# DAUGHTERBOARD.net
KiCad netlist of a schematic drawn in Altium Designer
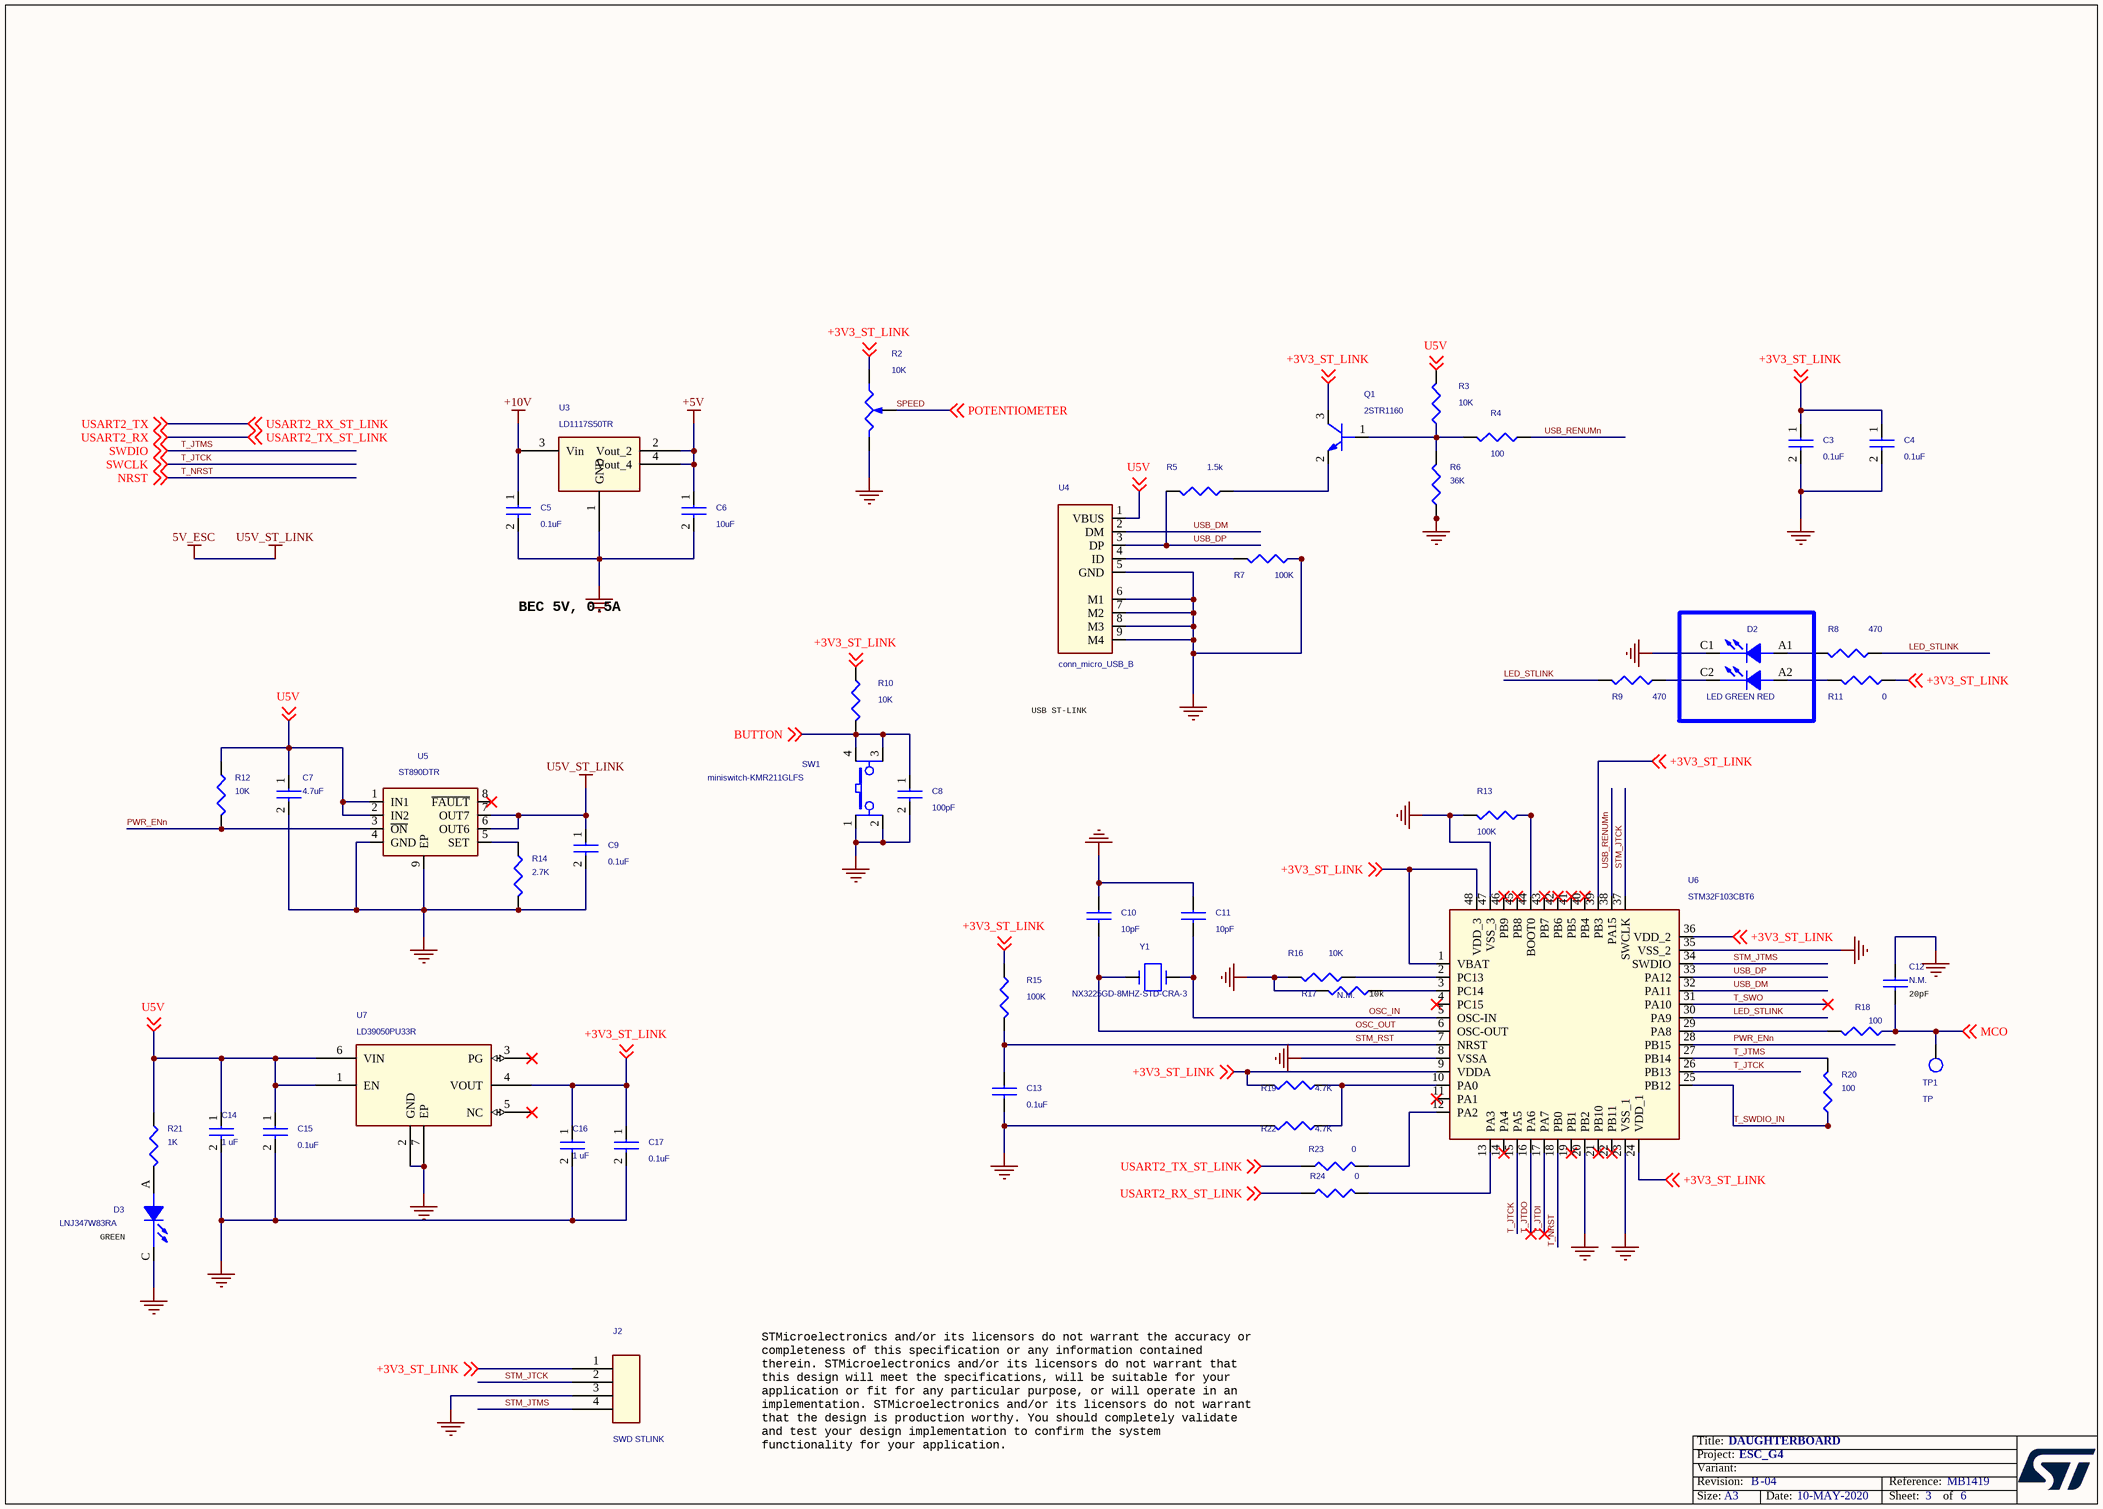
[diagram p0: DAUGHTERBOARD.SchDoc]

(export (version "E")
  (design (tool "Eeschema 10.0.6"))
  (components
    (comp (ref "C3")
      (value "0.1uF")
      (footprint "C_0402")
      (description "CAP CER 0.1UF 16V X7R 0402")
      (fields (field (name "MANUFACTURER") "Wurth Electronics Inc.") (field (name "TOLERANCE") "10%"))
      (libsource (lib "*") (part "CAP_Dup1"))
    )
    (comp (ref "C4")
      (value "0.1uF")
      (footprint "C_0402")
      (description "CAP CER 0.1UF 16V X7R 0402")
      (fields (field (name "MANUFACTURER") "Wurth Electronics Inc.") (field (name "TOLERANCE") "10%"))
      (libsource (lib "*") (part "CAP_Dup1"))
    )
    (comp (ref "C5")
      (value "0.1uF")
      (footprint "C_0402")
      (description "CAP CER 0.1UF 16V X7R 0402")
      (fields (field (name "MANUFACTURER") "Wurth Electronics Inc.") (field (name "TOLERANCE") "10%"))
      (libsource (lib "*") (part "CAP_Dup1"))
    )
    (comp (ref "C6")
      (value "10uF")
      (footprint "C_0805")
      (description "CAP CER 10UF 16V X5R 0805")
      (fields (field (name "MANUFACTURER") "Wurth Electronics Inc.") (field (name "TOLERANCE") "20%"))
      (libsource (lib "*") (part "CAP_Dup1"))
    )
    (comp (ref "C7")
      (value "4.7uF")
      (footprint "C_0805")
      (description "CAP CER 4.7UF 16V X5R 0805")
      (fields (field (name "PART_NUMBER") "TMP-410") (field (name "TOLERANCE") "20%"))
      (libsource (lib "*") (part "CAP_Dup1"))
    )
    (comp (ref "C8")
      (value "100pF")
      (footprint "C_0402")
      (description "CAP CER 100PF 10V C0G/NP0 0402")
      (fields (field (name "PART_NUMBER") "TMP-412") (field (name "TOLERANCE") "5%"))
      (libsource (lib "*") (part "CAP_Dup1"))
    )
    (comp (ref "C9")
      (value "0.1uF")
      (footprint "C_0402")
      (description "CAP CER 0.1UF 16V X7R 0402")
      (fields (field (name "MANUFACTURER") "Wurth Electronics Inc.") (field (name "TOLERANCE") "10%"))
      (libsource (lib "*") (part "CAP_Dup1"))
    )
    (comp (ref "C10")
      (value "10pF")
      (footprint "C_0402")
      (description "CAP CER 10PF 10V C0G/NP0 0402")
      (fields (field (name "PART_NUMBER") "TMP-395") (field (name "TOLERANCE") "5%"))
      (libsource (lib "*") (part "CAP_7"))
    )
    (comp (ref "C11")
      (value "10pF")
      (footprint "C_0402")
      (description "CAP CER 10PF 10V C0G/NP0 0402")
      (fields (field (name "PART_NUMBER") "TMP-395") (field (name "TOLERANCE") "5%"))
      (libsource (lib "*") (part "CAP_7"))
    )
    (comp (ref "C12")
      (value "N.M.")
      (footprint "C_0402")
      (description "CAP CER 0402-NOT MOUNTED")
      (fields (field (name "PART_NUMBER") "TMP-408"))
      (libsource (lib "*") (part "CAP_6"))
    )
    (comp (ref "C13")
      (value "0.1uF")
      (footprint "C_0402")
      (description "CAP CER 0.1UF 16V X7R 0402")
      (fields (field (name "PART_NUMBER") "CAP-00000053") (field (name "TOLERANCE") "10%"))
      (libsource (lib "*") (part "CAP_8"))
    )
    (comp (ref "C14")
      (value "1 uF")
      (footprint "C_0603")
      (description "CAP CER 1UF 16V X5R 0603")
      (fields (field (name "PART_NUMBER") "TMP-302") (field (name "TOLERANCE") "10%"))
      (libsource (lib "*") (part "CAP_Dup1"))
    )
    (comp (ref "C15")
      (value "0.1uF")
      (footprint "C_0603")
      (description "CAP CER 0.1UF 16V X7R 0603")
      (fields (field (name "MANUFACTURER") "Wurth Electronics Inc.") (field (name "TOLERANCE") "10%"))
      (libsource (lib "*") (part "CAP_Dup1"))
    )
    (comp (ref "C16")
      (value "1 uF")
      (footprint "C_0603")
      (description "CAP CER 1UF 16V X5R 0603")
      (fields (field (name "PART_NUMBER") "TMP-302") (field (name "TOLERANCE") "10%"))
      (libsource (lib "*") (part "CAP_Dup1"))
    )
    (comp (ref "C17")
      (value "0.1uF")
      (footprint "C_0402")
      (description "CAP CER 0.1UF 16V X7R 0402")
      (fields (field (name "PART_NUMBER") "CAP-00000053") (field (name "TOLERANCE") "10%"))
      (libsource (lib "*") (part "CAP_Dup1"))
    )
    (comp (ref "D2")
      (value "LED GREEN RED")
      (footprint "Led_bicolor_3528-PLCC-4")
      (description "LED GREEN/RED CLEAR 4PLCC SMD")
      (fields (field (name "PART_NUMBER") "TMP-705") (field (name "MANUFACTURER") "Wurth Electronics Inc."))
      (libsource (lib "*") (part "LED_BICOLOR"))
    )
    (comp (ref "D3")
      (value "LNJ347W83RA")
      (footprint "D_0402_Led_green")
      (description "LED GREEN 0402 SMD")
      (fields
        (field (name "MANUFACTURER") "Panasonic Electronic Components")
        (field (name "PART_NUMBER") "TMP-187")
      )
      (libsource (lib "*") (part "LED"))
    )
    (comp (ref "J2")
      (value "SWD STLINK")
      (footprint "strip4_100m_v")
      (description "SOLDER PADS")
      (libsource (lib "*") (part "CON4"))
    )
    (comp (ref "Q1")
      (value "2STR1160")
      (footprint "sot23-3p97_255x140l40x40n")
      (description "TRANS NPN 60V 1A SOT-23")
      (fields (field (name "PART_NUMBER") "TMP-433") (field (name "MANUFACTURER") "STMicroelectronics"))
      (libsource (lib "*") (part "BJT_NPN_BEC"))
    )
    (comp (ref "R2")
      (value "10K")
      (footprint "trimmer-3386P_T")
      (description "TRIMMER 10K OHM 0.5W PC PIN")
      (fields (field (name "PART_NUMBER") "TMP-491") (field (name "TOLERANCE") "10%"))
      (libsource (lib "*") (part "POT"))
    )
    (comp (ref "R3")
      (value "10K")
      (footprint "R_0402")
      (description "RES SMD 10K OHM 1% 1/16W 0402")
      (fields (field (name "MANUFACTURER") "Yageo") (field (name "TOLERANCE") "1%"))
      (libsource (lib "*") (part "RES"))
    )
    (comp (ref "R4")
      (value "100")
      (footprint "R_0402")
      (description "RES SMD 100 OHM 1% 1/16W 0402")
      (fields (field (name "PART_NUMBER") "TMP-406") (field (name "TOLERANCE") "1%"))
      (libsource (lib "*") (part "RES"))
    )
    (comp (ref "R5")
      (value "1.5k")
      (footprint "R_0402")
      (description "RES SMD 1.5K OHM 1% 1/16W 0402")
      (fields (field (name "PART_NUMBER") "TMP-393") (field (name "TOLERANCE") "1%"))
      (libsource (lib "*") (part "RES"))
    )
    (comp (ref "R6")
      (value "36K")
      (footprint "R_0402")
      (description "RES SMD 36K OHM 1% 1/16W 0402")
      (fields (field (name "MANUFACTURER") "Yageo") (field (name "TOLERANCE") "1%"))
      (libsource (lib "*") (part "RES"))
    )
    (comp (ref "R7")
      (value "100K")
      (footprint "R_0402")
      (description "RES SMD 100K OHM 1% 1/16W 0402")
      (fields (field (name "MANUFACTURER") "TE Connectivity Passive Product") (field (name "TOLERANCE") "1%"))
      (libsource (lib "*") (part "RES"))
    )
    (comp (ref "R8")
      (value "470")
      (footprint "R_0402")
      (description "RES SMD 100 OHM 1% 1/16W 0402")
      (fields (field (name "PART_NUMBER") "TMP-406") (field (name "TOLERANCE") "1%"))
      (libsource (lib "*") (part "RES"))
    )
    (comp (ref "R9")
      (value "470")
      (footprint "R_0402")
      (description "RES SMD 100 OHM 1% 1/16W 0402")
      (fields (field (name "MANUFACTURER") "TE Connectivity Passive Product") (field (name "TOLERANCE") "1%"))
      (libsource (lib "*") (part "RES"))
    )
    (comp (ref "R10")
      (value "10K")
      (footprint "R_0402")
      (description "RES SMD 10K OHM 1% 1/16W 0402")
      (fields (field (name "PART_NUMBER") "TMP-396") (field (name "TOLERANCE") "1%"))
      (libsource (lib "*") (part "RES"))
    )
    (comp (ref "R11")
      (value "0")
      (footprint "R_0402")
      (description "RES SMD 0 OHM JUMPER 1/16W 0402")
      (fields (field (name "MANUFACTURER") "Vishay Dale") (field (name "TOLERANCE") "Jumper"))
      (libsource (lib "*") (part "RES"))
    )
    (comp (ref "R12")
      (value "10K")
      (footprint "R_0402")
      (description "RES SMD 10K OHM 1% 1/16W 0402")
      (fields (field (name "MANUFACTURER") "Yageo") (field (name "TOLERANCE") "1%"))
      (libsource (lib "*") (part "RES"))
    )
    (comp (ref "R13")
      (value "100K")
      (footprint "R_0402")
      (description "RES SMD 100K OHM 1% 1/16W 0402")
      (fields (field (name "MANUFACTURER") "TE Connectivity Passive Product") (field (name "TOLERANCE") "1%"))
      (libsource (lib "*") (part "RES"))
    )
    (comp (ref "R14")
      (value "2.7K")
      (footprint "R_0402")
      (description "RES SMD 2.7K OHM 1% 1/16W 0402")
      (fields (field (name "PART_NUMBER") "TMP-411") (field (name "TOLERANCE") "1%"))
      (libsource (lib "*") (part "RES"))
    )
    (comp (ref "R15")
      (value "100K")
      (footprint "R_0402")
      (description "RES SMD 100K OHM 1% 1/16W 0402")
      (fields (field (name "PART_NUMBER") "TMP-405") (field (name "TOLERANCE") "1%"))
      (libsource (lib "*") (part "RES"))
    )
    (comp (ref "R16")
      (value "10K")
      (footprint "R_0402")
      (description "RES SMD 10K OHM 1% 1/16W 0402")
      (fields (field (name "PART_NUMBER") "TMP-396") (field (name "TOLERANCE") "1%"))
      (libsource (lib "*") (part "RES"))
    )
    (comp (ref "R17")
      (value "N.M.")
      (footprint "R_0402")
      (description "RES SMD 0402 - NOT MOUNTED")
      (fields (field (name "PART_NUMBER") "TMP-404"))
      (libsource (lib "*") (part "RES"))
    )
    (comp (ref "R18")
      (value "100")
      (footprint "R_0402")
      (description "RES SMD 100 OHM 1% 1/16W 0402")
      (fields (field (name "MANUFACTURER") "TE Connectivity Passive Product") (field (name "TOLERANCE") "1%"))
      (libsource (lib "*") (part "RES"))
    )
    (comp (ref "R19")
      (value "4.7K")
      (footprint "R_0402")
      (description "RES SMD 4.7K OHM 1% 1/16W 0402")
      (fields (field (name "PART_NUMBER") "TMP-403") (field (name "TOLERANCE") "1%"))
      (libsource (lib "*") (part "RES"))
    )
    (comp (ref "R20")
      (value "100")
      (footprint "R_0402")
      (description "RES SMD 100 OHM 1% 1/16W 0402")
      (fields (field (name "PART_NUMBER") "TMP-406") (field (name "TOLERANCE") "1%"))
      (libsource (lib "*") (part "RES"))
    )
    (comp (ref "R21")
      (value "1K")
      (footprint "R_0402")
      (description "RES SMD 1K OHM 1% 1/16W 0402")
      (fields (field (name "PART_NUMBER") "TMP-352") (field (name "TOLERANCE") "1%"))
      (libsource (lib "*") (part "RES"))
    )
    (comp (ref "R22")
      (value "4.7K")
      (footprint "R_0402")
      (description "RES SMD 4.7K OHM 1% 1/16W 0402")
      (fields (field (name "PART_NUMBER") "TMP-403") (field (name "TOLERANCE") "1%"))
      (libsource (lib "*") (part "RES"))
    )
    (comp (ref "R23")
      (value "0")
      (footprint "JUMPER_0603_DROP")
      (description "RES SMD 0 OHM JUMPER 1/10W 0603")
      (fields
        (field (name "MANUFACTURER") "Panasonic Electronic Components")
        (field (name "TOLERANCE") "Jumper")
      )
      (libsource (lib "*") (part "RES"))
    )
    (comp (ref "R24")
      (value "0")
      (footprint "JUMPER_0603_DROP")
      (description "RES SMD 0 OHM JUMPER 1/10W 0603")
      (fields (field (name "PART_NUMBER") "RES-00000056") (field (name "TOLERANCE") "Jumper"))
      (libsource (lib "*") (part "RES"))
    )
    (comp (ref "SW1")
      (value "miniswitch-KMR211GLFS")
      (footprint "switch_SMT_4_2x2_8mm")
      (description "SWITCH TACTILE SPST-NO 0.05A 32V")
      (fields (field (name "MANUFACTURER") "C&K") (field (name "PART_NUMBER") "TMP-285"))
      (libsource (lib "*") (part "PUSHBUTTON-SPST-2"))
    )
    (comp (ref "TP1")
      (value "TP")
      (footprint "test_point_100_smd")
      (description "TEST POINT 1MM  SMD PADSTASCK")
      (fields (field (name "PART_NUMBER") "TMP-386"))
      (libsource (lib "*") (part "TESTPOINT"))
    )
    (comp (ref "U3")
      (value "LD1117S50TR")
      (footprint "sot223-4p230_700x190l65x72")
      (description "IC REG LINEAR 5V 800MA SOT223")
      (fields (field (name "MANUFACTURER") "STMicroelectronics") (field (name "PART_NUMBER") "TMP-381"))
      (libsource (lib "*") (part "LD1117SxxxTR_0"))
    )
    (comp (ref "U4")
      (value "conn_micro_USB_B")
      (footprint "conn_micro_USB_B_SMD")
      (description "CONN RCPT 5POS MICRO USB R/A")
      (fields (field (name "MANUFACTURER") "Molex, LLC") (field (name "PART_NUMBER") "TMP-434"))
      (libsource (lib "*") (part "USB_MICRO"))
    )
    (comp (ref "U5")
      (value "ST890DTR")
      (footprint "son9p65_300x300x90l30x30t240-1")
      (description "IC PWR SWITCH 1.2A HISIDE 8-DFN")
      (fields (field (name "MANUFACTURER") "STMicroelectronics") (field (name "PART_NUMBER") "TMP-432"))
      (libsource (lib "*") (part "ST890DTR"))
    )
    (comp (ref "U6")
      (value "STM32F103CBT6")
      (footprint "qfp48p50_900x900x160l60x22n")
      (description "IC MCU 32BIT 128KB FLASH 48LQFP")
      (fields (field (name "PART_NUMBER") "TMP-399") (field (name "MANUFACTURER") "STMicroelectronics"))
      (libsource (lib "*") (part "STM32F103CBT6"))
    )
    (comp (ref "U7")
      (value "LD39050PU33R")
      (footprint "son7p95_300x300x100l40x34t23-1")
      (description "IC REG LINEAR 3.3V 500MA 6DFN")
      (fields (field (name "PART_NUMBER") "TMP-358") (field (name "MANUFACTURER") "STMicroelectronics"))
      (libsource (lib "*") (part "LD39050PU33R"))
    )
    (comp (ref "Y1")
      (value "NX3225GD-8MHZ-STD-CRA-3")
      (footprint "xtaldfn2_320x250x100l130x230")
      (description "CRYSTAL 8.0000MHZ 8PF SMD")
      (fields (field (name "MANUFACTURER") "NDK America, Inc.") (field (name "PART_NUMBER") "TMP-435"))
      (libsource (lib "*") (part "crystal"))
    )
  )
  (nets
    (net (code "1") (name "+3V3_ST_LINK") (class "Default")
      (node (ref "C16") (pin "1") (pinfunction "1_1") (pintype "passive"))
      (node (ref "C17") (pin "1") (pinfunction "1_1") (pintype "passive"))
      (node (ref "C3") (pin "1") (pinfunction "1_1") (pintype "passive"))
      (node (ref "C4") (pin "1") (pinfunction "1_1") (pintype "passive"))
      (node (ref "J2") (pin "1") (pinfunction "1_1") (pintype "passive"))
      (node (ref "Q1") (pin "3") (pinfunction "C_3") (pintype "passive"))
      (node (ref "R10") (pin "1") (pinfunction "1_1") (pintype "passive"))
      (node (ref "R11") (pin "1") (pinfunction "1_1") (pintype "passive"))
      (node (ref "R15") (pin "1") (pinfunction "1_1") (pintype "passive"))
      (node (ref "R19") (pin "2") (pinfunction "2_2") (pintype "passive"))
      (node (ref "R2") (pin "3") (pinfunction "B_3") (pintype "passive"))
      (node (ref "U6") (pin "1") (pinfunction "VBAT_1") (pintype "passive"))
      (node (ref "U6") (pin "24") (pinfunction "VDD_1_24") (pintype "passive"))
      (node (ref "U6") (pin "36") (pinfunction "VDD_2_36") (pintype "passive"))
      (node (ref "U6") (pin "39") (pinfunction "PB3_39") (pintype "passive"))
      (node (ref "U6") (pin "48") (pinfunction "VDD_3_48") (pintype "passive"))
      (node (ref "U6") (pin "9") (pinfunction "VDDA_9") (pintype "passive"))
      (node (ref "U7") (pin "4") (pinfunction "VOUT_4") (pintype "power_in"))
    )
    (net (code "2") (name "+5V") (class "Default")
      (node (ref "C6") (pin "1") (pinfunction "1_1") (pintype "passive"))
      (node (ref "U3") (pin "2") (pinfunction "Vout_2_2") (pintype "passive"))
      (node (ref "U3") (pin "4") (pinfunction "Vout_4_4") (pintype "passive"))
    )
    (net (code "3") (name "+10V") (class "Default")
      (node (ref "C5") (pin "1") (pinfunction "1_1") (pintype "passive"))
      (node (ref "U3") (pin "3") (pinfunction "Vin_3") (pintype "passive"))
    )
    (net (code "4") (name "/LED_STLINK") (class "Default")
      (node (ref "R8") (pin "1") (pinfunction "1_1") (pintype "passive"))
      (node (ref "R9") (pin "2") (pinfunction "2_2") (pintype "passive"))
      (node (ref "U6") (pin "30") (pinfunction "PA9_30") (pintype "passive"))
    )
    (net (code "5") (name "/OSC_IN") (class "Default")
      (node (ref "C11") (pin "2") (pinfunction "2_2") (pintype "passive"))
      (node (ref "U6") (pin "5") (pinfunction "OSC-IN_5") (pintype "passive"))
      (node (ref "Y1") (pin "1") (pinfunction "1_1") (pintype "passive"))
    )
    (net (code "6") (name "/OSC_OUT") (class "Default")
      (node (ref "C10") (pin "2") (pinfunction "2_2") (pintype "passive"))
      (node (ref "U6") (pin "6") (pinfunction "OSC-OUT_6") (pintype "passive"))
      (node (ref "Y1") (pin "2") (pinfunction "2_2") (pintype "passive"))
    )
    (net (code "7") (name "/PWR_ENn") (class "Default")
      (node (ref "R12") (pin "2") (pinfunction "2_2") (pintype "passive"))
      (node (ref "U5") (pin "3") (pinfunction "~{ON}_3") (pintype "passive"))
      (node (ref "U6") (pin "28") (pinfunction "PB15_28") (pintype "passive"))
    )
    (net (code "8") (name "/STM_JTCK") (class "Default")
      (node (ref "J2") (pin "2") (pinfunction "2_2") (pintype "passive"))
      (node (ref "U6") (pin "37") (pinfunction "SWCLK_37") (pintype "passive"))
    )
    (net (code "9") (name "/STM_JTMS") (class "Default")
      (node (ref "J2") (pin "4") (pinfunction "4_4") (pintype "passive"))
      (node (ref "U6") (pin "34") (pinfunction "SWDIO_34") (pintype "passive"))
    )
    (net (code "10") (name "/STM_RST") (class "Default")
      (node (ref "C13") (pin "1") (pinfunction "1_1") (pintype "passive"))
      (node (ref "R15") (pin "2") (pinfunction "2_2") (pintype "passive"))
      (node (ref "U6") (pin "7") (pinfunction "NRST_7") (pintype "passive"))
    )
    (net (code "11") (name "/T_JTDI") (class "Default")
      (node (ref "U6") (pin "17") (pinfunction "PA7_17") (pintype "passive+no_connect"))
    )
    (net (code "12") (name "/T_JTDO") (class "Default")
      (node (ref "U6") (pin "16") (pinfunction "PA6_16") (pintype "passive+no_connect"))
    )
    (net (code "13") (name "/T_SWDIO_IN") (class "Default")
      (node (ref "R20") (pin "1") (pinfunction "1_1") (pintype "passive"))
      (node (ref "U6") (pin "25") (pinfunction "PB12_25") (pintype "passive"))
    )
    (net (code "14") (name "/T_SWO") (class "Default")
      (node (ref "U6") (pin "31") (pinfunction "PA10_31") (pintype "passive+no_connect"))
    )
    (net (code "15") (name "/USB_DM") (class "Default")
      (node (ref "U4") (pin "2") (pinfunction "DM_2") (pintype "passive"))
      (node (ref "U6") (pin "32") (pinfunction "PA11_32") (pintype "passive"))
    )
    (net (code "16") (name "/USB_DP") (class "Default")
      (node (ref "R5") (pin "2") (pinfunction "2_2") (pintype "passive"))
      (node (ref "U4") (pin "3") (pinfunction "DP_3") (pintype "passive"))
      (node (ref "U6") (pin "33") (pinfunction "PA12_33") (pintype "passive"))
    )
    (net (code "17") (name "/USB_RENUMn") (class "Default")
      (node (ref "R4") (pin "1") (pinfunction "1_1") (pintype "passive"))
      (node (ref "U6") (pin "38") (pinfunction "PA15_38") (pintype "passive"))
    )
    (net (code "18") (name "5V_ESC") (class "Default")
      (node (ref "C9") (pin "1") (pinfunction "1_1") (pintype "passive"))
      (node (ref "U5") (pin "6") (pinfunction "OUT6_6") (pintype "passive"))
      (node (ref "U5") (pin "7") (pinfunction "OUT7_7") (pintype "passive"))
    )
    (net (code "19") (name "BUTTON") (class "Default")
      (node (ref "C8") (pin "1") (pinfunction "1_1") (pintype "passive"))
      (node (ref "R10") (pin "2") (pinfunction "2_2") (pintype "passive"))
      (node (ref "SW1") (pin "3") (pinfunction "3_3") (pintype "passive"))
      (node (ref "SW1") (pin "4") (pinfunction "4_4") (pintype "passive"))
    )
    (net (code "20") (name "GND") (class "Default")
      (node (ref "C10") (pin "1") (pinfunction "1_1") (pintype "passive"))
      (node (ref "C11") (pin "1") (pinfunction "1_1") (pintype "passive"))
      (node (ref "C12") (pin "1") (pinfunction "1_1") (pintype "passive"))
      (node (ref "C13") (pin "2") (pinfunction "2_2") (pintype "passive"))
      (node (ref "C14") (pin "2") (pinfunction "2_2") (pintype "passive"))
      (node (ref "C15") (pin "2") (pinfunction "2_2") (pintype "passive"))
      (node (ref "C16") (pin "2") (pinfunction "2_2") (pintype "passive"))
      (node (ref "C17") (pin "2") (pinfunction "2_2") (pintype "passive"))
      (node (ref "C3") (pin "2") (pinfunction "2_2") (pintype "passive"))
      (node (ref "C4") (pin "2") (pinfunction "2_2") (pintype "passive"))
      (node (ref "C5") (pin "2") (pinfunction "2_2") (pintype "passive"))
      (node (ref "C6") (pin "2") (pinfunction "2_2") (pintype "passive"))
      (node (ref "C7") (pin "2") (pinfunction "2_2") (pintype "passive"))
      (node (ref "C8") (pin "2") (pinfunction "2_2") (pintype "passive"))
      (node (ref "C9") (pin "2") (pinfunction "2_2") (pintype "passive"))
      (node (ref "D2") (pin "C1") (pinfunction "CATHODE1_C1") (pintype "passive"))
      (node (ref "D3") (pin "C") (pinfunction "CATHODE_C") (pintype "passive"))
      (node (ref "J2") (pin "3") (pinfunction "3_3") (pintype "passive"))
      (node (ref "R13") (pin "2") (pinfunction "2_2") (pintype "passive"))
      (node (ref "R14") (pin "2") (pinfunction "2_2") (pintype "passive"))
      (node (ref "R16") (pin "2") (pinfunction "2_2") (pintype "passive"))
      (node (ref "R17") (pin "2") (pinfunction "2_2") (pintype "passive"))
      (node (ref "R2") (pin "1") (pinfunction "A_1") (pintype "passive"))
      (node (ref "R22") (pin "2") (pinfunction "2_2") (pintype "passive"))
      (node (ref "R6") (pin "1") (pinfunction "1_1") (pintype "passive"))
      (node (ref "R7") (pin "1") (pinfunction "1_1") (pintype "passive"))
      (node (ref "SW1") (pin "1") (pinfunction "1_1") (pintype "passive"))
      (node (ref "SW1") (pin "2") (pinfunction "2_2") (pintype "passive"))
      (node (ref "U3") (pin "1") (pinfunction "GND_1") (pintype "power_in"))
      (node (ref "U4") (pin "5") (pinfunction "GND_5") (pintype "passive"))
      (node (ref "U4") (pin "6") (pinfunction "M1_6") (pintype "passive"))
      (node (ref "U4") (pin "7") (pinfunction "M2_7") (pintype "passive"))
      (node (ref "U4") (pin "8") (pinfunction "M3_8") (pintype "passive"))
      (node (ref "U4") (pin "9") (pinfunction "M4_9") (pintype "passive"))
      (node (ref "U5") (pin "4") (pinfunction "GND_4") (pintype "passive"))
      (node (ref "U5") (pin "9") (pinfunction "EP_9") (pintype "passive"))
      (node (ref "U6") (pin "20") (pinfunction "PB2_20") (pintype "passive"))
      (node (ref "U6") (pin "23") (pinfunction "VSS_1_23") (pintype "passive"))
      (node (ref "U6") (pin "35") (pinfunction "VSS_2_35") (pintype "passive"))
      (node (ref "U6") (pin "47") (pinfunction "VSS_3_47") (pintype "passive"))
      (node (ref "U6") (pin "8") (pinfunction "VSSA_8") (pintype "passive"))
      (node (ref "U7") (pin "2") (pinfunction "GND_2") (pintype "power_in"))
      (node (ref "U7") (pin "7") (pinfunction "EP_7") (pintype "power_in"))
    )
    (net (code "21") (name "MCO") (class "Default")
      (node (ref "C12") (pin "2") (pinfunction "2_2") (pintype "passive"))
      (node (ref "R18") (pin "1") (pinfunction "1_1") (pintype "passive"))
      (node (ref "TP1") (pin "1") (pinfunction "1_1") (pintype "passive"))
    )
    (net (code "22") (name "NRST") (class "Default")
      (node (ref "U6") (pin "18") (pinfunction "PB0_18") (pintype "passive"))
    )
    (net (code "23") (name "Net-(D2-ANODE1)") (class "Default")
      (node (ref "D2") (pin "A1") (pinfunction "ANODE1_A1") (pintype "passive"))
      (node (ref "R8") (pin "2") (pinfunction "2_2") (pintype "passive"))
    )
    (net (code "24") (name "Net-(D2-ANODE2)") (class "Default")
      (node (ref "D2") (pin "A2") (pinfunction "ANODE2_A2") (pintype "passive"))
      (node (ref "R11") (pin "2") (pinfunction "2_2") (pintype "passive"))
    )
    (net (code "25") (name "Net-(D2-CATHODE2)") (class "Default")
      (node (ref "D2") (pin "C2") (pinfunction "CATHODE2_C2") (pintype "passive"))
      (node (ref "R9") (pin "1") (pinfunction "1_1") (pintype "passive"))
    )
    (net (code "26") (name "Net-(D3-ANODE)") (class "Default")
      (node (ref "D3") (pin "A") (pinfunction "ANODE_A") (pintype "passive"))
      (node (ref "R21") (pin "2") (pinfunction "2_2") (pintype "passive"))
    )
    (net (code "27") (name "Net-(Q1-B)") (class "Default")
      (node (ref "Q1") (pin "1") (pinfunction "B_1") (pintype "passive"))
      (node (ref "R3") (pin "1") (pinfunction "1_1") (pintype "passive"))
      (node (ref "R4") (pin "2") (pinfunction "2_2") (pintype "passive"))
      (node (ref "R6") (pin "2") (pinfunction "2_2") (pintype "passive"))
    )
    (net (code "28") (name "Net-(Q1-E)") (class "Default")
      (node (ref "Q1") (pin "2") (pinfunction "E_2") (pintype "passive"))
      (node (ref "R5") (pin "1") (pinfunction "1_1") (pintype "passive"))
    )
    (net (code "29") (name "Net-(U4-ID)") (class "Default")
      (node (ref "R7") (pin "2") (pinfunction "2_2") (pintype "passive"))
      (node (ref "U4") (pin "4") (pinfunction "ID_4") (pintype "passive"))
    )
    (net (code "30") (name "Net-(U5-SET)") (class "Default")
      (node (ref "R14") (pin "1") (pinfunction "1_1") (pintype "passive"))
      (node (ref "U5") (pin "5") (pinfunction "SET_5") (pintype "passive"))
    )
    (net (code "31") (name "Net-(U6-BOOT0)") (class "Default")
      (node (ref "R13") (pin "1") (pinfunction "1_1") (pintype "passive"))
      (node (ref "U6") (pin "44") (pinfunction "BOOT0_44") (pintype "passive"))
    )
    (net (code "32") (name "Net-(U6-PA0)") (class "Default")
      (node (ref "R19") (pin "1") (pinfunction "1_1") (pintype "passive"))
      (node (ref "R22") (pin "1") (pinfunction "1_1") (pintype "passive"))
      (node (ref "U6") (pin "10") (pinfunction "PA0_10") (pintype "passive"))
    )
    (net (code "33") (name "Net-(U6-PA2)") (class "Default")
      (node (ref "R23") (pin "2") (pinfunction "2_2") (pintype "passive"))
      (node (ref "U6") (pin "12") (pinfunction "PA2_12") (pintype "passive"))
    )
    (net (code "34") (name "Net-(U6-PA3)") (class "Default")
      (node (ref "R24") (pin "2") (pinfunction "2_2") (pintype "passive"))
      (node (ref "U6") (pin "13") (pinfunction "PA3_13") (pintype "passive"))
    )
    (net (code "35") (name "Net-(U6-PA8)") (class "Default")
      (node (ref "R18") (pin "2") (pinfunction "2_2") (pintype "passive"))
      (node (ref "U6") (pin "29") (pinfunction "PA8_29") (pintype "passive"))
    )
    (net (code "36") (name "Net-(U6-PC13)") (class "Default")
      (node (ref "R16") (pin "1") (pinfunction "1_1") (pintype "passive"))
      (node (ref "U6") (pin "2") (pinfunction "PC13_2") (pintype "passive"))
    )
    (net (code "37") (name "Net-(U6-PC14)") (class "Default")
      (node (ref "R17") (pin "1") (pinfunction "1_1") (pintype "passive"))
      (node (ref "U6") (pin "3") (pinfunction "PC14_3") (pintype "passive"))
    )
    (net (code "38") (name "POTENTIOMETER") (class "Default")
      (node (ref "R2") (pin "2") (pinfunction "WIPER_2") (pintype "passive"))
    )
    (net (code "39") (name "SWCLK") (class "Default")
      (node (ref "U6") (pin "15") (pinfunction "PA5_15") (pintype "passive"))
      (node (ref "U6") (pin "26") (pinfunction "PB13_26") (pintype "passive"))
    )
    (net (code "40") (name "SWDIO") (class "Default")
      (node (ref "R20") (pin "2") (pinfunction "2_2") (pintype "passive"))
      (node (ref "U6") (pin "27") (pinfunction "PB14_27") (pintype "passive"))
    )
    (net (code "41") (name "U5V") (class "Default")
      (node (ref "C14") (pin "1") (pinfunction "1_1") (pintype "passive"))
      (node (ref "C15") (pin "1") (pinfunction "1_1") (pintype "passive"))
      (node (ref "C7") (pin "1") (pinfunction "1_1") (pintype "passive"))
      (node (ref "R12") (pin "1") (pinfunction "1_1") (pintype "passive"))
      (node (ref "R21") (pin "1") (pinfunction "1_1") (pintype "passive"))
      (node (ref "R3") (pin "2") (pinfunction "2_2") (pintype "passive"))
      (node (ref "U4") (pin "1") (pinfunction "VBUS_1") (pintype "passive"))
      (node (ref "U5") (pin "1") (pinfunction "IN1_1") (pintype "passive"))
      (node (ref "U5") (pin "2") (pinfunction "IN2_2") (pintype "passive"))
      (node (ref "U7") (pin "1") (pinfunction "EN_1") (pintype "power_in"))
      (node (ref "U7") (pin "6") (pinfunction "VIN_6") (pintype "power_in"))
    )
    (net (code "42") (name "USART2_RX") (class "Default")
      (node (ref "R23") (pin "1") (pinfunction "1_1") (pintype "passive"))
    )
    (net (code "43") (name "USART2_RX_ST_LINK") (class "Default")
      (node (ref "R24") (pin "1") (pinfunction "1_1") (pintype "passive"))
    )
    (net (code "44") (name "unconnected-(U5-~{FAULT}-Pad8)") (class "Default")
      (node (ref "U5") (pin "8") (pinfunction "~{FAULT}_8") (pintype "passive+no_connect"))
    )
    (net (code "45") (name "unconnected-(U6-PA1-Pad11)") (class "Default")
      (node (ref "U6") (pin "11") (pinfunction "PA1_11") (pintype "passive+no_connect"))
    )
    (net (code "46") (name "unconnected-(U6-PA4-Pad14)") (class "Default")
      (node (ref "U6") (pin "14") (pinfunction "PA4_14") (pintype "passive+no_connect"))
    )
    (net (code "47") (name "unconnected-(U6-PB1-Pad19)") (class "Default")
      (node (ref "U6") (pin "19") (pinfunction "PB1_19") (pintype "passive+no_connect"))
    )
    (net (code "48") (name "unconnected-(U6-PB4-Pad40)") (class "Default")
      (node (ref "U6") (pin "40") (pinfunction "PB4_40") (pintype "passive+no_connect"))
    )
    (net (code "49") (name "unconnected-(U6-PB5-Pad41)") (class "Default")
      (node (ref "U6") (pin "41") (pinfunction "PB5_41") (pintype "passive+no_connect"))
    )
    (net (code "50") (name "unconnected-(U6-PB6-Pad42)") (class "Default")
      (node (ref "U6") (pin "42") (pinfunction "PB6_42") (pintype "passive+no_connect"))
    )
    (net (code "51") (name "unconnected-(U6-PB7-Pad43)") (class "Default")
      (node (ref "U6") (pin "43") (pinfunction "PB7_43") (pintype "passive+no_connect"))
    )
    (net (code "52") (name "unconnected-(U6-PB8-Pad45)") (class "Default")
      (node (ref "U6") (pin "45") (pinfunction "PB8_45") (pintype "passive+no_connect"))
    )
    (net (code "53") (name "unconnected-(U6-PB9-Pad46)") (class "Default")
      (node (ref "U6") (pin "46") (pinfunction "PB9_46") (pintype "passive+no_connect"))
    )
    (net (code "54") (name "unconnected-(U6-PB10-Pad21)") (class "Default")
      (node (ref "U6") (pin "21") (pinfunction "PB10_21") (pintype "passive+no_connect"))
    )
    (net (code "55") (name "unconnected-(U6-PB11-Pad22)") (class "Default")
      (node (ref "U6") (pin "22") (pinfunction "PB11_22") (pintype "passive+no_connect"))
    )
    (net (code "56") (name "unconnected-(U6-PC15-Pad4)") (class "Default")
      (node (ref "U6") (pin "4") (pinfunction "PC15_4") (pintype "passive+no_connect"))
    )
    (net (code "57") (name "unconnected-(U7-NC-Pad5)") (class "Default")
      (node (ref "U7") (pin "5") (pinfunction "NC_5") (pintype "bidirectional+no_connect"))
    )
    (net (code "58") (name "unconnected-(U7-PG-Pad3)") (class "Default")
      (node (ref "U7") (pin "3") (pinfunction "PG_3") (pintype "bidirectional+no_connect"))
    )
  )
)
